# stm32-devboard.net
KiCad netlist of a schematic drawn in EasyEDA Pro
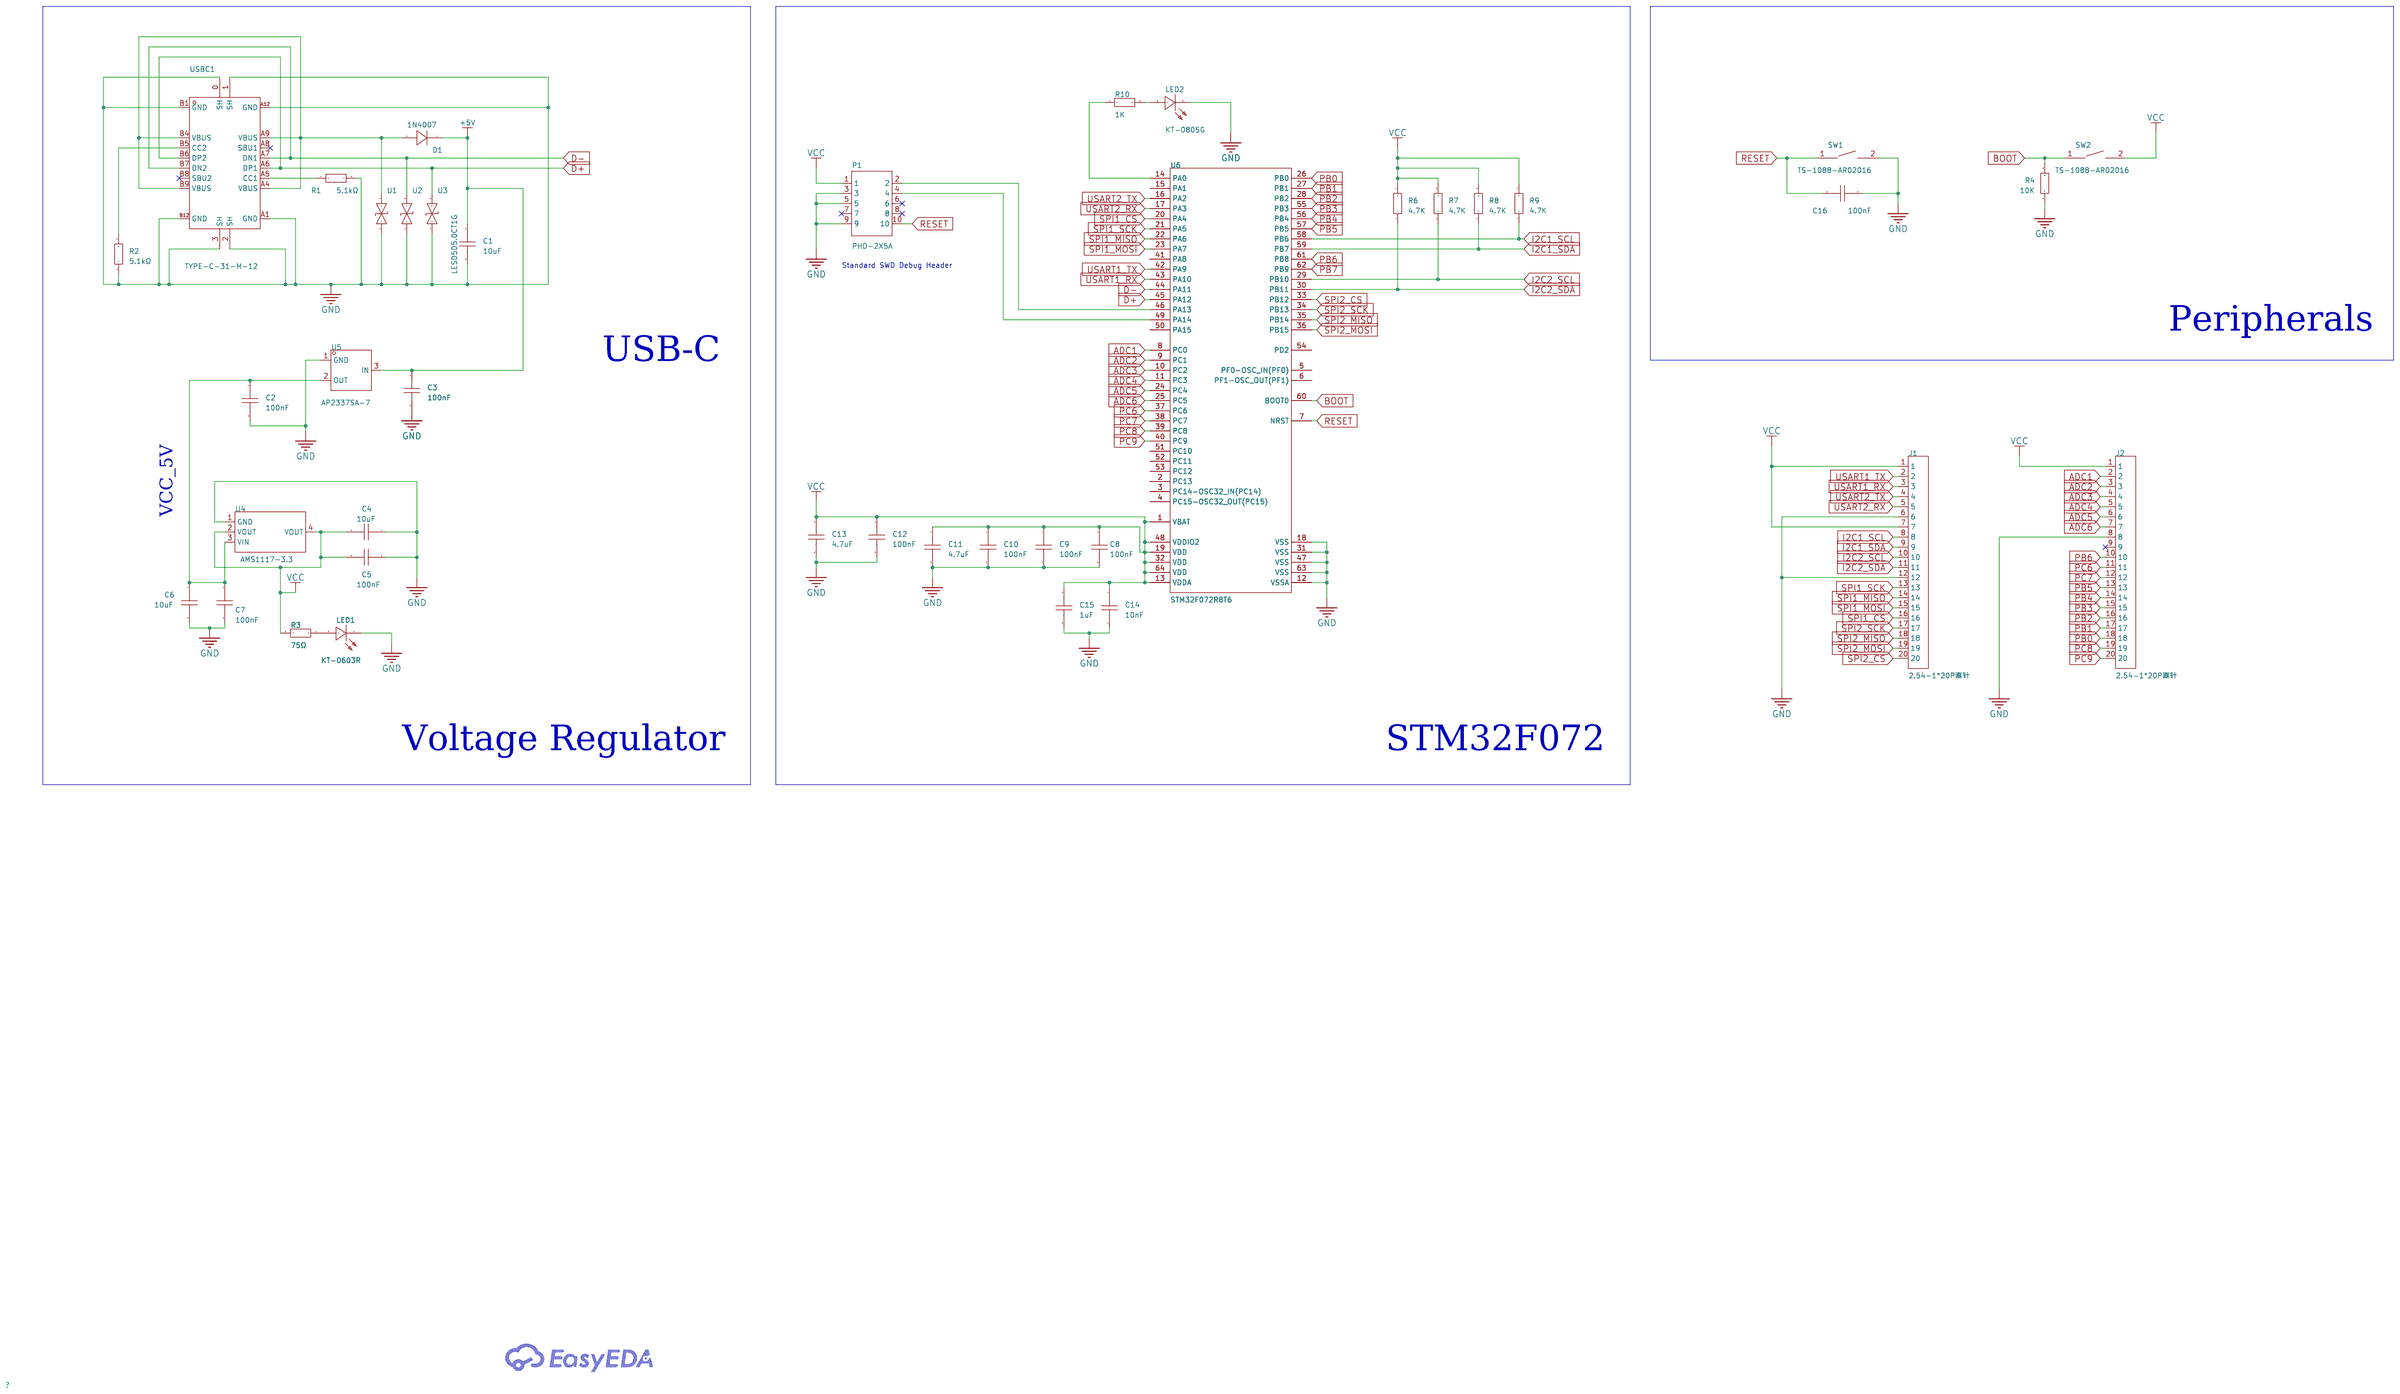
[diagram p0: schematic sheet]

(export (version "E")
  (design (tool "Eeschema 10.0.6"))
  (components
    (comp (ref "C1")
      (value "10uF")
      (footprint "easyedapro:C0603")
      (description "Capacitance:10uF Tolerance:±10% Tolerance:±10% Voltage Rating:10V Temperature Coefficient:X5R")
      (fields
        (field (name "Manufacturer Part") "CL10A106KP8NNNC")
        (field (name "Manufacturer") "SAMSUNG(三星)")
      )
      (libsource (lib "easyedapro") (part "CAP"))
    )
    (comp (ref "C2")
      (value "100nF")
      (footprint "easyedapro:C0603")
      (description "Capacitance:100nF Tolerance:±10% Tolerance:±10% Voltage Rating:50V Temperature Coefficient:X7R")
      (fields
        (field (name "Manufacturer Part") "CC0603KRX7R9BB104")
        (field (name "Manufacturer") "YAGEO(国巨)")
      )
      (libsource (lib "easyedapro") (part "CAP"))
    )
    (comp (ref "C3")
      (value "100nF")
      (footprint "easyedapro:C0603")
      (description "Capacitance:100nF Tolerance:±10% Tolerance:±10% Voltage Rating:50V Temperature Coefficient:X7R")
      (fields
        (field (name "Manufacturer Part") "CC0603KRX7R9BB104")
        (field (name "Manufacturer") "YAGEO(国巨)")
      )
      (libsource (lib "easyedapro") (part "CAP"))
    )
    (comp (ref "C4")
      (value "10uF")
      (footprint "easyedapro:C0603")
      (description "Capacitance:10uF Tolerance:±10% Tolerance:±10% Voltage Rating:10V Temperature Coefficient:X5R")
      (fields
        (field (name "Manufacturer Part") "CL10A106KP8NNNC")
        (field (name "Manufacturer") "SAMSUNG(三星)")
      )
      (libsource (lib "easyedapro") (part "CAP"))
    )
    (comp (ref "C5")
      (value "100nF")
      (footprint "easyedapro:C0603")
      (description "Capacitance:100nF Tolerance:±10% Tolerance:±10% Voltage Rating:50V Temperature Coefficient:X7R")
      (fields
        (field (name "Manufacturer Part") "CC0603KRX7R9BB104")
        (field (name "Manufacturer") "YAGEO(国巨)")
      )
      (libsource (lib "easyedapro") (part "CAP"))
    )
    (comp (ref "C6")
      (value "10uF")
      (footprint "easyedapro:C0603")
      (description "Capacitance:10uF Tolerance:±10% Tolerance:±10% Voltage Rating:10V Temperature Coefficient:X5R")
      (fields
        (field (name "Manufacturer Part") "CL10A106KP8NNNC")
        (field (name "Manufacturer") "SAMSUNG(三星)")
      )
      (libsource (lib "easyedapro") (part "CAP"))
    )
    (comp (ref "C7")
      (value "100nF")
      (footprint "easyedapro:C0603")
      (description "Capacitance:100nF Tolerance:±10% Tolerance:±10% Voltage Rating:50V Temperature Coefficient:X7R")
      (fields
        (field (name "Manufacturer Part") "CC0603KRX7R9BB104")
        (field (name "Manufacturer") "YAGEO(国巨)")
      )
      (libsource (lib "easyedapro") (part "CAP"))
    )
    (comp (ref "C8")
      (value "100nF")
      (footprint "easyedapro:C0603")
      (libsource (lib "easyedapro") (part "CAP"))
    )
    (comp (ref "C9")
      (value "100nF")
      (footprint "easyedapro:C0603")
      (libsource (lib "easyedapro") (part "CAP"))
    )
    (comp (ref "C10")
      (value "100nF")
      (footprint "easyedapro:C0603")
      (libsource (lib "easyedapro") (part "CAP"))
    )
    (comp (ref "C11")
      (value "4.7uF")
      (footprint "easyedapro:C0603")
      (libsource (lib "easyedapro") (part "CAP"))
    )
    (comp (ref "C12")
      (value "100nF")
      (footprint "easyedapro:C0603")
      (libsource (lib "easyedapro") (part "CAP"))
    )
    (comp (ref "C13")
      (value "4.7uF")
      (footprint "easyedapro:C0603")
      (libsource (lib "easyedapro") (part "CAP"))
    )
    (comp (ref "C14")
      (value "10nF")
      (footprint "easyedapro:C0603")
      (libsource (lib "easyedapro") (part "CAP"))
    )
    (comp (ref "C15")
      (value "1uF")
      (footprint "easyedapro:C0603")
      (libsource (lib "easyedapro") (part "CAP"))
    )
    (comp (ref "C16")
      (value "100nF")
      (footprint "easyedapro:C0603")
      (libsource (lib "easyedapro") (part "CAP"))
    )
    (comp (ref "D1")
      (value "1N4007")
      (footprint "easyedapro:SMA_L4.3-W2.5-LS5.0-RD")
      (fields (field (name "Manufacturer") "TWGMC(迪嘉)"))
      (libsource (lib "easyedapro") (part "1N4007_C727081"))
    )
    (comp (ref "J1")
      (value "2.54-1*20P直针")
      (footprint "easyedapro:HDR-TH_20P-P2.54-V-M-1")
      (fields (field (name "Manufacturer") "BOOMELE(博穆精密)"))
      (libsource (lib "easyedapro") (part "Header-Male-2.54_1x20"))
    )
    (comp (ref "J2")
      (value "2.54-1*20P直针")
      (footprint "easyedapro:HDR-TH_20P-P2.54-V-M-1")
      (fields (field (name "Manufacturer") "BOOMELE(博穆精密)"))
      (libsource (lib "easyedapro") (part "Header-Male-2.54_1x20"))
    )
    (comp (ref "LED1")
      (value "KT-0603R")
      (footprint "easyedapro:LED0603-RD")
      (fields (field (name "Manufacturer") "KENTO"))
      (libsource (lib "easyedapro") (part "KT-0603R"))
    )
    (comp (ref "LED2")
      (value "KT-0805G")
      (footprint "easyedapro:LED0805-R-RD")
      (fields (field (name "Manufacturer") "KENTO"))
      (libsource (lib "easyedapro") (part "0805G (Green)"))
    )
    (comp (ref "P1")
      (value "PHD-2X5A")
      (footprint "easyedapro:CONN-TH_10P-P2.00_PHD2.0MM-2X5")
      (fields (field (name "Manufacturer") "BOOMELE(博穆精密)"))
      (libsource (lib "easyedapro") (part "PHD2.0mm-2X5,header"))
    )
    (comp (ref "R1")
      (value "5.1kΩ")
      (footprint "easyedapro:R0603")
      (fields
        (field (name "Manufacturer Part") "0603WAF5101T5E")
        (field (name "Manufacturer") "UNI-ROYAL(厚声)")
      )
      (libsource (lib "easyedapro") (part "Res"))
    )
    (comp (ref "R2")
      (value "5.1kΩ")
      (footprint "easyedapro:R0603")
      (fields
        (field (name "Manufacturer Part") "0603WAF5101T5E")
        (field (name "Manufacturer") "UNI-ROYAL(厚声)")
      )
      (libsource (lib "easyedapro") (part "Res"))
    )
    (comp (ref "R3")
      (value "75Ω")
      (footprint "easyedapro:R0603")
      (fields
        (field (name "Manufacturer Part") "0603WAF750JT5E")
        (field (name "Manufacturer") "UNI-ROYAL(厚声)")
      )
      (libsource (lib "easyedapro") (part "Res"))
    )
    (comp (ref "R4") (value "10K") (footprint "easyedapro:R0603") (libsource (lib "easyedapro") (part "Res")))
    (comp (ref "R6")
      (value "4.7K")
      (footprint "easyedapro:R0603")
      (libsource (lib "easyedapro") (part "Res"))
    )
    (comp (ref "R7")
      (value "4.7K")
      (footprint "easyedapro:R0603")
      (libsource (lib "easyedapro") (part "Res"))
    )
    (comp (ref "R8")
      (value "4.7K")
      (footprint "easyedapro:R0603")
      (libsource (lib "easyedapro") (part "Res"))
    )
    (comp (ref "R9")
      (value "4.7K")
      (footprint "easyedapro:R0603")
      (libsource (lib "easyedapro") (part "Res"))
    )
    (comp (ref "R10") (value "1K") (footprint "easyedapro:R0603") (libsource (lib "easyedapro") (part "Res")))
    (comp (ref "SW1")
      (value "TS-1088-AR02016")
      (footprint "easyedapro:SW-SMD_L3.9-W3.0-P4.45")
      (fields (field (name "Manufacturer") "XUNPU(讯普)"))
      (libsource (lib "easyedapro") (part "TS-1088-AR02016"))
    )
    (comp (ref "SW2")
      (value "TS-1088-AR02016")
      (footprint "easyedapro:SW-SMD_L3.9-W3.0-P4.45")
      (fields (field (name "Manufacturer") "XUNPU(讯普)"))
      (libsource (lib "easyedapro") (part "TS-1088-AR02016"))
    )
    (comp (ref "U1")
      (value "LESD5D5.0CT1G")
      (footprint "easyedapro:SOD-523_L1.2-W0.8-LS1.6-BI")
      (fields (field (name "Manufacturer") "Leiditech(雷卯电子)"))
      (libsource (lib "easyedapro") (part "LESD5D5.0CT1G_C5246195"))
    )
    (comp (ref "U2")
      (value "LESD5D5.0CT1G")
      (footprint "easyedapro:SOD-523_L1.2-W0.8-LS1.6-BI")
      (fields (field (name "Manufacturer") "Leiditech(雷卯电子)"))
      (libsource (lib "easyedapro") (part "LESD5D5.0CT1G_C5246195"))
    )
    (comp (ref "U3")
      (value "LESD5D5.0CT1G")
      (footprint "easyedapro:SOD-523_L1.2-W0.8-LS1.6-BI")
      (fields (field (name "Manufacturer") "Leiditech(雷卯电子)"))
      (libsource (lib "easyedapro") (part "LESD5D5.0CT1G_C5246195"))
    )
    (comp (ref "U4")
      (value "AMS1117-3.3")
      (footprint "easyedapro:SOT-223-3_L6.5-W3.4-P2.30-LS7.0-BR")
      (fields (field (name "Manufacturer") "AMS"))
      (libsource (lib "easyedapro") (part "AMS1117-3.3"))
    )
    (comp (ref "U5")
      (value "AP2337SA-7")
      (footprint "easyedapro:SOT-23-3_L2.9-W1.3-P1.90-LS2.4-BR")
      (fields (field (name "Manufacturer") "DIODES(美台)"))
      (libsource (lib "easyedapro") (part "AP2337SA-7"))
    )
    (comp (ref "U6")
      (value "STM32F072R8T6")
      (footprint "easyedapro:LQFP-64_L10.0-W10.0-P0.50-LS12.0-BL")
      (fields (field (name "Manufacturer") "ST(意法半导体)"))
      (libsource (lib "easyedapro") (part "STM32F072R8T6"))
    )
    (comp (ref "USBC1")
      (value "TYPE-C-31-M-12")
      (footprint "easyedapro:USB-C_SMD-TYPE-C-31-M-12")
      (fields (field (name "Manufacturer") "韩国韩荣"))
      (libsource (lib "easyedapro") (part "TYPE-C-31-M-12"))
    )
  )
  (nets
    (net (code "1") (name "+5V") (class "Default")
      (node (ref "C1") (pin "1") (pinfunction "1_1") (pintype "input"))
      (node (ref "C3") (pin "1") (pinfunction "1_1") (pintype "input"))
      (node (ref "D1") (pin "1") (pinfunction "K_1") (pintype "unspecified"))
      (node (ref "U5") (pin "3") (pinfunction "IN_3") (pintype "input"))
    )
    (net (code "2") (name "ADC1") (class "Default")
      (node (ref "J2") (pin "2") (pinfunction "2_2") (pintype "unspecified"))
      (node (ref "U6") (pin "8") (pinfunction "PC0_8") (pintype "bidirectional"))
    )
    (net (code "3") (name "ADC2") (class "Default")
      (node (ref "J2") (pin "3") (pinfunction "3_3") (pintype "unspecified"))
      (node (ref "U6") (pin "9") (pinfunction "PC1_9") (pintype "bidirectional"))
    )
    (net (code "4") (name "ADC3") (class "Default")
      (node (ref "J2") (pin "4") (pinfunction "4_4") (pintype "unspecified"))
      (node (ref "U6") (pin "10") (pinfunction "PC2_10") (pintype "bidirectional"))
    )
    (net (code "5") (name "ADC4") (class "Default")
      (node (ref "J2") (pin "5") (pinfunction "5_5") (pintype "unspecified"))
      (node (ref "U6") (pin "11") (pinfunction "PC3_11") (pintype "bidirectional"))
    )
    (net (code "6") (name "ADC5") (class "Default")
      (node (ref "J2") (pin "6") (pinfunction "6_6") (pintype "unspecified"))
      (node (ref "U6") (pin "24") (pinfunction "PC4_24") (pintype "bidirectional"))
    )
    (net (code "7") (name "ADC6") (class "Default")
      (node (ref "J2") (pin "7") (pinfunction "7_7") (pintype "unspecified"))
      (node (ref "U6") (pin "25") (pinfunction "PC5_25") (pintype "bidirectional"))
    )
    (net (code "8") (name "BOOT") (class "Default")
      (node (ref "R4") (pin "2") (pinfunction "2_2") (pintype "input"))
      (node (ref "SW2") (pin "1") (pinfunction "1_1") (pintype "unspecified"))
      (node (ref "U6") (pin "60") (pinfunction "BOOT0_60") (pintype "input"))
    )
    (net (code "9") (name "D+") (class "Default")
      (node (ref "U3") (pin "2") (pinfunction "2_2") (pintype "unspecified"))
      (node (ref "U6") (pin "45") (pinfunction "PA12_45") (pintype "bidirectional"))
      (node (ref "USBC1") (pin "A6") (pinfunction "DP1_A6") (pintype "unspecified"))
      (node (ref "USBC1") (pin "B6") (pinfunction "DP2_B6") (pintype "unspecified"))
    )
    (net (code "10") (name "D-") (class "Default")
      (node (ref "U2") (pin "2") (pinfunction "2_2") (pintype "unspecified"))
      (node (ref "U6") (pin "44") (pinfunction "PA11_44") (pintype "bidirectional"))
      (node (ref "USBC1") (pin "A7") (pinfunction "DN1_A7") (pintype "unspecified"))
      (node (ref "USBC1") (pin "B7") (pinfunction "DN2_B7") (pintype "unspecified"))
    )
    (net (code "11") (name "GND") (class "Default")
      (node (ref "C1") (pin "2") (pinfunction "2_2") (pintype "input"))
      (node (ref "C10") (pin "2") (pinfunction "2_2") (pintype "input"))
      (node (ref "C11") (pin "2") (pinfunction "2_2") (pintype "input"))
      (node (ref "C12") (pin "2") (pinfunction "2_2") (pintype "input"))
      (node (ref "C13") (pin "2") (pinfunction "2_2") (pintype "input"))
      (node (ref "C14") (pin "2") (pinfunction "2_2") (pintype "input"))
      (node (ref "C15") (pin "2") (pinfunction "2_2") (pintype "input"))
      (node (ref "C16") (pin "1") (pinfunction "1_1") (pintype "input"))
      (node (ref "C2") (pin "2") (pinfunction "2_2") (pintype "input"))
      (node (ref "C3") (pin "2") (pinfunction "2_2") (pintype "input"))
      (node (ref "C4") (pin "1") (pinfunction "1_1") (pintype "input"))
      (node (ref "C5") (pin "1") (pinfunction "1_1") (pintype "input"))
      (node (ref "C6") (pin "2") (pinfunction "2_2") (pintype "input"))
      (node (ref "C7") (pin "2") (pinfunction "2_2") (pintype "input"))
      (node (ref "C8") (pin "2") (pinfunction "2_2") (pintype "input"))
      (node (ref "C9") (pin "2") (pinfunction "2_2") (pintype "input"))
      (node (ref "J1") (pin "12") (pinfunction "12_12") (pintype "unspecified"))
      (node (ref "J1") (pin "6") (pinfunction "6_6") (pintype "unspecified"))
      (node (ref "J2") (pin "8") (pinfunction "8_8") (pintype "unspecified"))
      (node (ref "LED1") (pin "1") (pinfunction "K_1") (pintype "unspecified"))
      (node (ref "LED2") (pin "2") (pinfunction "K_2") (pintype "unspecified"))
      (node (ref "P1") (pin "3") (pinfunction "3_3") (pintype "unspecified"))
      (node (ref "P1") (pin "5") (pinfunction "5_5") (pintype "unspecified"))
      (node (ref "P1") (pin "9") (pinfunction "9_9") (pintype "unspecified"))
      (node (ref "R1") (pin "2") (pinfunction "2_2") (pintype "input"))
      (node (ref "R2") (pin "1") (pinfunction "1_1") (pintype "input"))
      (node (ref "R4") (pin "1") (pinfunction "1_1") (pintype "input"))
      (node (ref "SW1") (pin "2") (pinfunction "2_2") (pintype "unspecified"))
      (node (ref "U1") (pin "1") (pinfunction "1_1") (pintype "unspecified"))
      (node (ref "U2") (pin "1") (pinfunction "1_1") (pintype "unspecified"))
      (node (ref "U3") (pin "1") (pinfunction "1_1") (pintype "unspecified"))
      (node (ref "U4") (pin "1") (pinfunction "GND_1") (pintype "unspecified"))
      (node (ref "U5") (pin "1") (pinfunction "GND_1") (pintype "input"))
      (node (ref "U6") (pin "12") (pinfunction "VSSA_12") (pintype "unspecified"))
      (node (ref "U6") (pin "18") (pinfunction "VSS_18") (pintype "unspecified"))
      (node (ref "U6") (pin "31") (pinfunction "VSS_31") (pintype "unspecified"))
      (node (ref "U6") (pin "47") (pinfunction "VSS_47") (pintype "unspecified"))
      (node (ref "U6") (pin "63") (pinfunction "VSS_63") (pintype "unspecified"))
      (node (ref "USBC1") (pin "0") (pinfunction "SH_0") (pintype "unspecified"))
      (node (ref "USBC1") (pin "1") (pinfunction "SH_1") (pintype "unspecified"))
      (node (ref "USBC1") (pin "2") (pinfunction "SH_2") (pintype "unspecified"))
      (node (ref "USBC1") (pin "3") (pinfunction "SH_3") (pintype "unspecified"))
      (node (ref "USBC1") (pin "A1") (pinfunction "GND_A1") (pintype "unspecified"))
      (node (ref "USBC1") (pin "A12") (pinfunction "GND_A12") (pintype "unspecified"))
      (node (ref "USBC1") (pin "B1") (pinfunction "GND_B1") (pintype "unspecified"))
      (node (ref "USBC1") (pin "B12") (pinfunction "GND_B12") (pintype "unspecified"))
    )
    (net (code "12") (name "I2C1_SCL") (class "Default")
      (node (ref "J1") (pin "8") (pinfunction "8_8") (pintype "unspecified"))
      (node (ref "R9") (pin "1") (pinfunction "1_1") (pintype "input"))
      (node (ref "U6") (pin "58") (pinfunction "PB6_58") (pintype "bidirectional"))
    )
    (net (code "13") (name "I2C1_SDA") (class "Default")
      (node (ref "J1") (pin "9") (pinfunction "9_9") (pintype "unspecified"))
      (node (ref "R8") (pin "1") (pinfunction "1_1") (pintype "input"))
      (node (ref "U6") (pin "59") (pinfunction "PB7_59") (pintype "bidirectional"))
    )
    (net (code "14") (name "I2C2_SCL") (class "Default")
      (node (ref "J1") (pin "10") (pinfunction "10_10") (pintype "unspecified"))
      (node (ref "R7") (pin "1") (pinfunction "1_1") (pintype "input"))
      (node (ref "U6") (pin "29") (pinfunction "PB10_29") (pintype "bidirectional"))
    )
    (net (code "15") (name "I2C2_SDA") (class "Default")
      (node (ref "J1") (pin "11") (pinfunction "11_11") (pintype "unspecified"))
      (node (ref "R6") (pin "1") (pinfunction "1_1") (pintype "input"))
      (node (ref "U6") (pin "30") (pinfunction "PB11_30") (pintype "bidirectional"))
    )
    (net (code "16") (name "Net-(D1-A)") (class "Default")
      (node (ref "D1") (pin "2") (pinfunction "A_2") (pintype "unspecified"))
      (node (ref "U1") (pin "2") (pinfunction "2_2") (pintype "unspecified"))
      (node (ref "USBC1") (pin "A4") (pinfunction "VBUS_A4") (pintype "unspecified"))
      (node (ref "USBC1") (pin "A9") (pinfunction "VBUS_A9") (pintype "unspecified"))
      (node (ref "USBC1") (pin "B4") (pinfunction "VBUS_B4") (pintype "unspecified"))
      (node (ref "USBC1") (pin "B9") (pinfunction "VBUS_B9") (pintype "unspecified"))
    )
    (net (code "17") (name "Net-(LED1-A)") (class "Default")
      (node (ref "LED1") (pin "2") (pinfunction "A_2") (pintype "unspecified"))
      (node (ref "R3") (pin "1") (pinfunction "1_1") (pintype "input"))
    )
    (net (code "18") (name "Net-(LED2-A)") (class "Default")
      (node (ref "LED2") (pin "1") (pinfunction "A_1") (pintype "unspecified"))
      (node (ref "R10") (pin "2") (pinfunction "2_2") (pintype "input"))
    )
    (net (code "19") (name "Net-(U4-VIN)") (class "Default")
      (node (ref "C2") (pin "1") (pinfunction "1_1") (pintype "input"))
      (node (ref "C6") (pin "1") (pinfunction "1_1") (pintype "input"))
      (node (ref "C7") (pin "1") (pinfunction "1_1") (pintype "input"))
      (node (ref "U4") (pin "3") (pinfunction "VIN_3") (pintype "unspecified"))
      (node (ref "U5") (pin "2") (pinfunction "OUT_2") (pintype "input"))
    )
    (net (code "20") (name "Net-(U6-PA0)") (class "Default")
      (node (ref "R10") (pin "1") (pinfunction "1_1") (pintype "input"))
      (node (ref "U6") (pin "14") (pinfunction "PA0_14") (pintype "bidirectional"))
    )
    (net (code "21") (name "Net-(U6-PA13)") (class "Default")
      (node (ref "P1") (pin "2") (pinfunction "2_2") (pintype "unspecified"))
      (node (ref "U6") (pin "46") (pinfunction "PA13_46") (pintype "bidirectional"))
    )
    (net (code "22") (name "Net-(U6-PA14)") (class "Default")
      (node (ref "P1") (pin "4") (pinfunction "4_4") (pintype "unspecified"))
      (node (ref "U6") (pin "49") (pinfunction "PA14_49") (pintype "bidirectional"))
    )
    (net (code "23") (name "Net-(USBC1-CC1)") (class "Default")
      (node (ref "R1") (pin "1") (pinfunction "1_1") (pintype "input"))
      (node (ref "USBC1") (pin "A5") (pinfunction "CC1_A5") (pintype "unspecified"))
    )
    (net (code "24") (name "Net-(USBC1-CC2)") (class "Default")
      (node (ref "R2") (pin "2") (pinfunction "2_2") (pintype "input"))
      (node (ref "USBC1") (pin "B5") (pinfunction "CC2_B5") (pintype "unspecified"))
    )
    (net (code "25") (name "PB0") (class "Default")
      (node (ref "J2") (pin "18") (pinfunction "18_18") (pintype "unspecified"))
      (node (ref "U6") (pin "26") (pinfunction "PB0_26") (pintype "bidirectional"))
    )
    (net (code "26") (name "PB1") (class "Default")
      (node (ref "J2") (pin "17") (pinfunction "17_17") (pintype "unspecified"))
      (node (ref "U6") (pin "27") (pinfunction "PB1_27") (pintype "bidirectional"))
    )
    (net (code "27") (name "PB2") (class "Default")
      (node (ref "J2") (pin "16") (pinfunction "16_16") (pintype "unspecified"))
      (node (ref "U6") (pin "28") (pinfunction "PB2_28") (pintype "bidirectional"))
    )
    (net (code "28") (name "PB3") (class "Default")
      (node (ref "J2") (pin "15") (pinfunction "15_15") (pintype "unspecified"))
      (node (ref "U6") (pin "55") (pinfunction "PB3_55") (pintype "bidirectional"))
    )
    (net (code "29") (name "PB4") (class "Default")
      (node (ref "J2") (pin "14") (pinfunction "14_14") (pintype "unspecified"))
      (node (ref "U6") (pin "56") (pinfunction "PB4_56") (pintype "bidirectional"))
    )
    (net (code "30") (name "PB5") (class "Default")
      (node (ref "J2") (pin "13") (pinfunction "13_13") (pintype "unspecified"))
      (node (ref "U6") (pin "57") (pinfunction "PB5_57") (pintype "bidirectional"))
    )
    (net (code "31") (name "PB6") (class "Default")
      (node (ref "J2") (pin "10") (pinfunction "10_10") (pintype "unspecified"))
      (node (ref "U6") (pin "61") (pinfunction "PB8_61") (pintype "bidirectional"))
    )
    (net (code "32") (name "PB7") (class "Default")
      (node (ref "U6") (pin "62") (pinfunction "PB9_62") (pintype "bidirectional"))
    )
    (net (code "33") (name "PC6") (class "Default")
      (node (ref "J2") (pin "11") (pinfunction "11_11") (pintype "unspecified"))
      (node (ref "U6") (pin "37") (pinfunction "PC6_37") (pintype "bidirectional"))
    )
    (net (code "34") (name "PC7") (class "Default")
      (node (ref "J2") (pin "12") (pinfunction "12_12") (pintype "unspecified"))
      (node (ref "U6") (pin "38") (pinfunction "PC7_38") (pintype "bidirectional"))
    )
    (net (code "35") (name "PC8") (class "Default")
      (node (ref "J2") (pin "19") (pinfunction "19_19") (pintype "unspecified"))
      (node (ref "U6") (pin "39") (pinfunction "PC8_39") (pintype "bidirectional"))
    )
    (net (code "36") (name "PC9") (class "Default")
      (node (ref "J2") (pin "20") (pinfunction "20_20") (pintype "unspecified"))
      (node (ref "U6") (pin "40") (pinfunction "PC9_40") (pintype "bidirectional"))
    )
    (net (code "37") (name "RESET") (class "Default")
      (node (ref "C16") (pin "2") (pinfunction "2_2") (pintype "input"))
      (node (ref "P1") (pin "10") (pinfunction "10_10") (pintype "unspecified"))
      (node (ref "SW1") (pin "1") (pinfunction "1_1") (pintype "unspecified"))
      (node (ref "U6") (pin "7") (pinfunction "NRST_7") (pintype "bidirectional"))
    )
    (net (code "38") (name "SPI1_CS") (class "Default")
      (node (ref "J1") (pin "16") (pinfunction "16_16") (pintype "unspecified"))
      (node (ref "U6") (pin "20") (pinfunction "PA4_20") (pintype "bidirectional"))
    )
    (net (code "39") (name "SPI1_MISO") (class "Default")
      (node (ref "J1") (pin "14") (pinfunction "14_14") (pintype "unspecified"))
      (node (ref "U6") (pin "22") (pinfunction "PA6_22") (pintype "bidirectional"))
    )
    (net (code "40") (name "SPI1_MOSI") (class "Default")
      (node (ref "J1") (pin "15") (pinfunction "15_15") (pintype "unspecified"))
      (node (ref "U6") (pin "23") (pinfunction "PA7_23") (pintype "bidirectional"))
    )
    (net (code "41") (name "SPI1_SCK") (class "Default")
      (node (ref "J1") (pin "13") (pinfunction "13_13") (pintype "unspecified"))
      (node (ref "U6") (pin "21") (pinfunction "PA5_21") (pintype "bidirectional"))
    )
    (net (code "42") (name "SPI2_CS") (class "Default")
      (node (ref "J1") (pin "20") (pinfunction "20_20") (pintype "unspecified"))
      (node (ref "U6") (pin "33") (pinfunction "PB12_33") (pintype "bidirectional"))
    )
    (net (code "43") (name "SPI2_MISO") (class "Default")
      (node (ref "J1") (pin "18") (pinfunction "18_18") (pintype "unspecified"))
      (node (ref "U6") (pin "35") (pinfunction "PB14_35") (pintype "bidirectional"))
    )
    (net (code "44") (name "SPI2_MOSI") (class "Default")
      (node (ref "J1") (pin "19") (pinfunction "19_19") (pintype "unspecified"))
      (node (ref "U6") (pin "36") (pinfunction "PB15_36") (pintype "bidirectional"))
    )
    (net (code "45") (name "SPI2_SCK") (class "Default")
      (node (ref "J1") (pin "17") (pinfunction "17_17") (pintype "unspecified"))
      (node (ref "U6") (pin "34") (pinfunction "PB13_34") (pintype "bidirectional"))
    )
    (net (code "46") (name "USART1_RX") (class "Default")
      (node (ref "J1") (pin "3") (pinfunction "3_3") (pintype "unspecified"))
      (node (ref "U6") (pin "43") (pinfunction "PA10_43") (pintype "bidirectional"))
    )
    (net (code "47") (name "USART1_TX") (class "Default")
      (node (ref "J1") (pin "2") (pinfunction "2_2") (pintype "unspecified"))
      (node (ref "U6") (pin "42") (pinfunction "PA9_42") (pintype "bidirectional"))
    )
    (net (code "48") (name "USART2_RX") (class "Default")
      (node (ref "J1") (pin "5") (pinfunction "5_5") (pintype "unspecified"))
      (node (ref "U6") (pin "17") (pinfunction "PA3_17") (pintype "bidirectional"))
    )
    (net (code "49") (name "USART2_TX") (class "Default")
      (node (ref "J1") (pin "4") (pinfunction "4_4") (pintype "unspecified"))
      (node (ref "U6") (pin "16") (pinfunction "PA2_16") (pintype "bidirectional"))
    )
    (net (code "50") (name "VCC") (class "Default")
      (node (ref "C10") (pin "1") (pinfunction "1_1") (pintype "input"))
      (node (ref "C11") (pin "1") (pinfunction "1_1") (pintype "input"))
      (node (ref "C12") (pin "1") (pinfunction "1_1") (pintype "input"))
      (node (ref "C13") (pin "1") (pinfunction "1_1") (pintype "input"))
      (node (ref "C14") (pin "1") (pinfunction "1_1") (pintype "input"))
      (node (ref "C15") (pin "1") (pinfunction "1_1") (pintype "input"))
      (node (ref "C4") (pin "2") (pinfunction "2_2") (pintype "input"))
      (node (ref "C5") (pin "2") (pinfunction "2_2") (pintype "input"))
      (node (ref "C8") (pin "1") (pinfunction "1_1") (pintype "input"))
      (node (ref "C9") (pin "1") (pinfunction "1_1") (pintype "input"))
      (node (ref "J1") (pin "1") (pinfunction "1_1") (pintype "unspecified"))
      (node (ref "J1") (pin "7") (pinfunction "7_7") (pintype "unspecified"))
      (node (ref "J2") (pin "1") (pinfunction "1_1") (pintype "unspecified"))
      (node (ref "P1") (pin "1") (pinfunction "1_1") (pintype "unspecified"))
      (node (ref "R3") (pin "2") (pinfunction "2_2") (pintype "input"))
      (node (ref "R6") (pin "2") (pinfunction "2_2") (pintype "input"))
      (node (ref "R7") (pin "2") (pinfunction "2_2") (pintype "input"))
      (node (ref "R8") (pin "2") (pinfunction "2_2") (pintype "input"))
      (node (ref "R9") (pin "2") (pinfunction "2_2") (pintype "input"))
      (node (ref "SW2") (pin "2") (pinfunction "2_2") (pintype "unspecified"))
      (node (ref "U4") (pin "2") (pinfunction "VOUT_2") (pintype "unspecified"))
      (node (ref "U4") (pin "4") (pinfunction "VOUT_4") (pintype "unspecified"))
      (node (ref "U6") (pin "1") (pinfunction "VBAT_1") (pintype "unspecified"))
      (node (ref "U6") (pin "13") (pinfunction "VDDA_13") (pintype "unspecified"))
      (node (ref "U6") (pin "19") (pinfunction "VDD_19") (pintype "unspecified"))
      (node (ref "U6") (pin "32") (pinfunction "VDD_32") (pintype "unspecified"))
      (node (ref "U6") (pin "48") (pinfunction "VDDIO2_48") (pintype "unspecified"))
      (node (ref "U6") (pin "64") (pinfunction "VDD_64") (pintype "unspecified"))
    )
    (net (code "51") (name "unconnected-(J2-Pad9)") (class "Default")
      (node (ref "J2") (pin "9") (pinfunction "9_9") (pintype "unspecified+no_connect"))
    )
    (net (code "52") (name "unconnected-(P1-Pad6)") (class "Default")
      (node (ref "P1") (pin "6") (pinfunction "6_6") (pintype "unspecified+no_connect"))
    )
    (net (code "53") (name "unconnected-(P1-Pad7)") (class "Default")
      (node (ref "P1") (pin "7") (pinfunction "7_7") (pintype "unspecified+no_connect"))
    )
    (net (code "54") (name "unconnected-(P1-Pad8)") (class "Default")
      (node (ref "P1") (pin "8") (pinfunction "8_8") (pintype "unspecified+no_connect"))
    )
    (net (code "55") (name "unconnected-(U6-PA1-Pad15)") (class "Default")
      (node (ref "U6") (pin "15") (pinfunction "PA1_15") (pintype "bidirectional"))
    )
    (net (code "56") (name "unconnected-(U6-PA8-Pad41)") (class "Default")
      (node (ref "U6") (pin "41") (pinfunction "PA8_41") (pintype "bidirectional"))
    )
    (net (code "57") (name "unconnected-(U6-PA15-Pad50)") (class "Default")
      (node (ref "U6") (pin "50") (pinfunction "PA15_50") (pintype "bidirectional"))
    )
    (net (code "58") (name "unconnected-(U6-PC10-Pad51)") (class "Default")
      (node (ref "U6") (pin "51") (pinfunction "PC10_51") (pintype "bidirectional"))
    )
    (net (code "59") (name "unconnected-(U6-PC11-Pad52)") (class "Default")
      (node (ref "U6") (pin "52") (pinfunction "PC11_52") (pintype "bidirectional"))
    )
    (net (code "60") (name "unconnected-(U6-PC12-Pad53)") (class "Default")
      (node (ref "U6") (pin "53") (pinfunction "PC12_53") (pintype "bidirectional"))
    )
    (net (code "61") (name "unconnected-(U6-PC13-Pad2)") (class "Default")
      (node (ref "U6") (pin "2") (pinfunction "PC13_2") (pintype "bidirectional"))
    )
    (net (code "62") (name "unconnected-(U6-PC14-OSC32_IN(PC14)-Pad3)") (class "Default")
      (node (ref "U6") (pin "3") (pinfunction "PC14-OSC32_IN(PC14)_3") (pintype "bidirectional"))
    )
    (net (code "63") (name "unconnected-(U6-PC15-OSC32_OUT(PC15)-Pad4)") (class "Default")
      (node (ref "U6") (pin "4") (pinfunction "PC15-OSC32_OUT(PC15)_4") (pintype "bidirectional"))
    )
    (net (code "64") (name "unconnected-(U6-PD2-Pad54)") (class "Default")
      (node (ref "U6") (pin "54") (pinfunction "PD2_54") (pintype "bidirectional"))
    )
    (net (code "65") (name "unconnected-(U6-PF0-OSC_IN(PF0)-Pad5)") (class "Default")
      (node (ref "U6") (pin "5") (pinfunction "PF0-OSC_IN(PF0)_5") (pintype "bidirectional"))
    )
    (net (code "66") (name "unconnected-(U6-PF1-OSC_OUT(PF1)-Pad6)") (class "Default")
      (node (ref "U6") (pin "6") (pinfunction "PF1-OSC_OUT(PF1)_6") (pintype "bidirectional"))
    )
    (net (code "67") (name "unconnected-(USBC1-SBU1-PadA8)") (class "Default")
      (node (ref "USBC1") (pin "A8") (pinfunction "SBU1_A8") (pintype "unspecified+no_connect"))
    )
    (net (code "68") (name "unconnected-(USBC1-SBU2-PadB8)") (class "Default")
      (node (ref "USBC1") (pin "B8") (pinfunction "SBU2_B8") (pintype "unspecified+no_connect"))
    )
  )
)
